# controller_mini.net
KiCad netlist of a schematic drawn in EAGLE
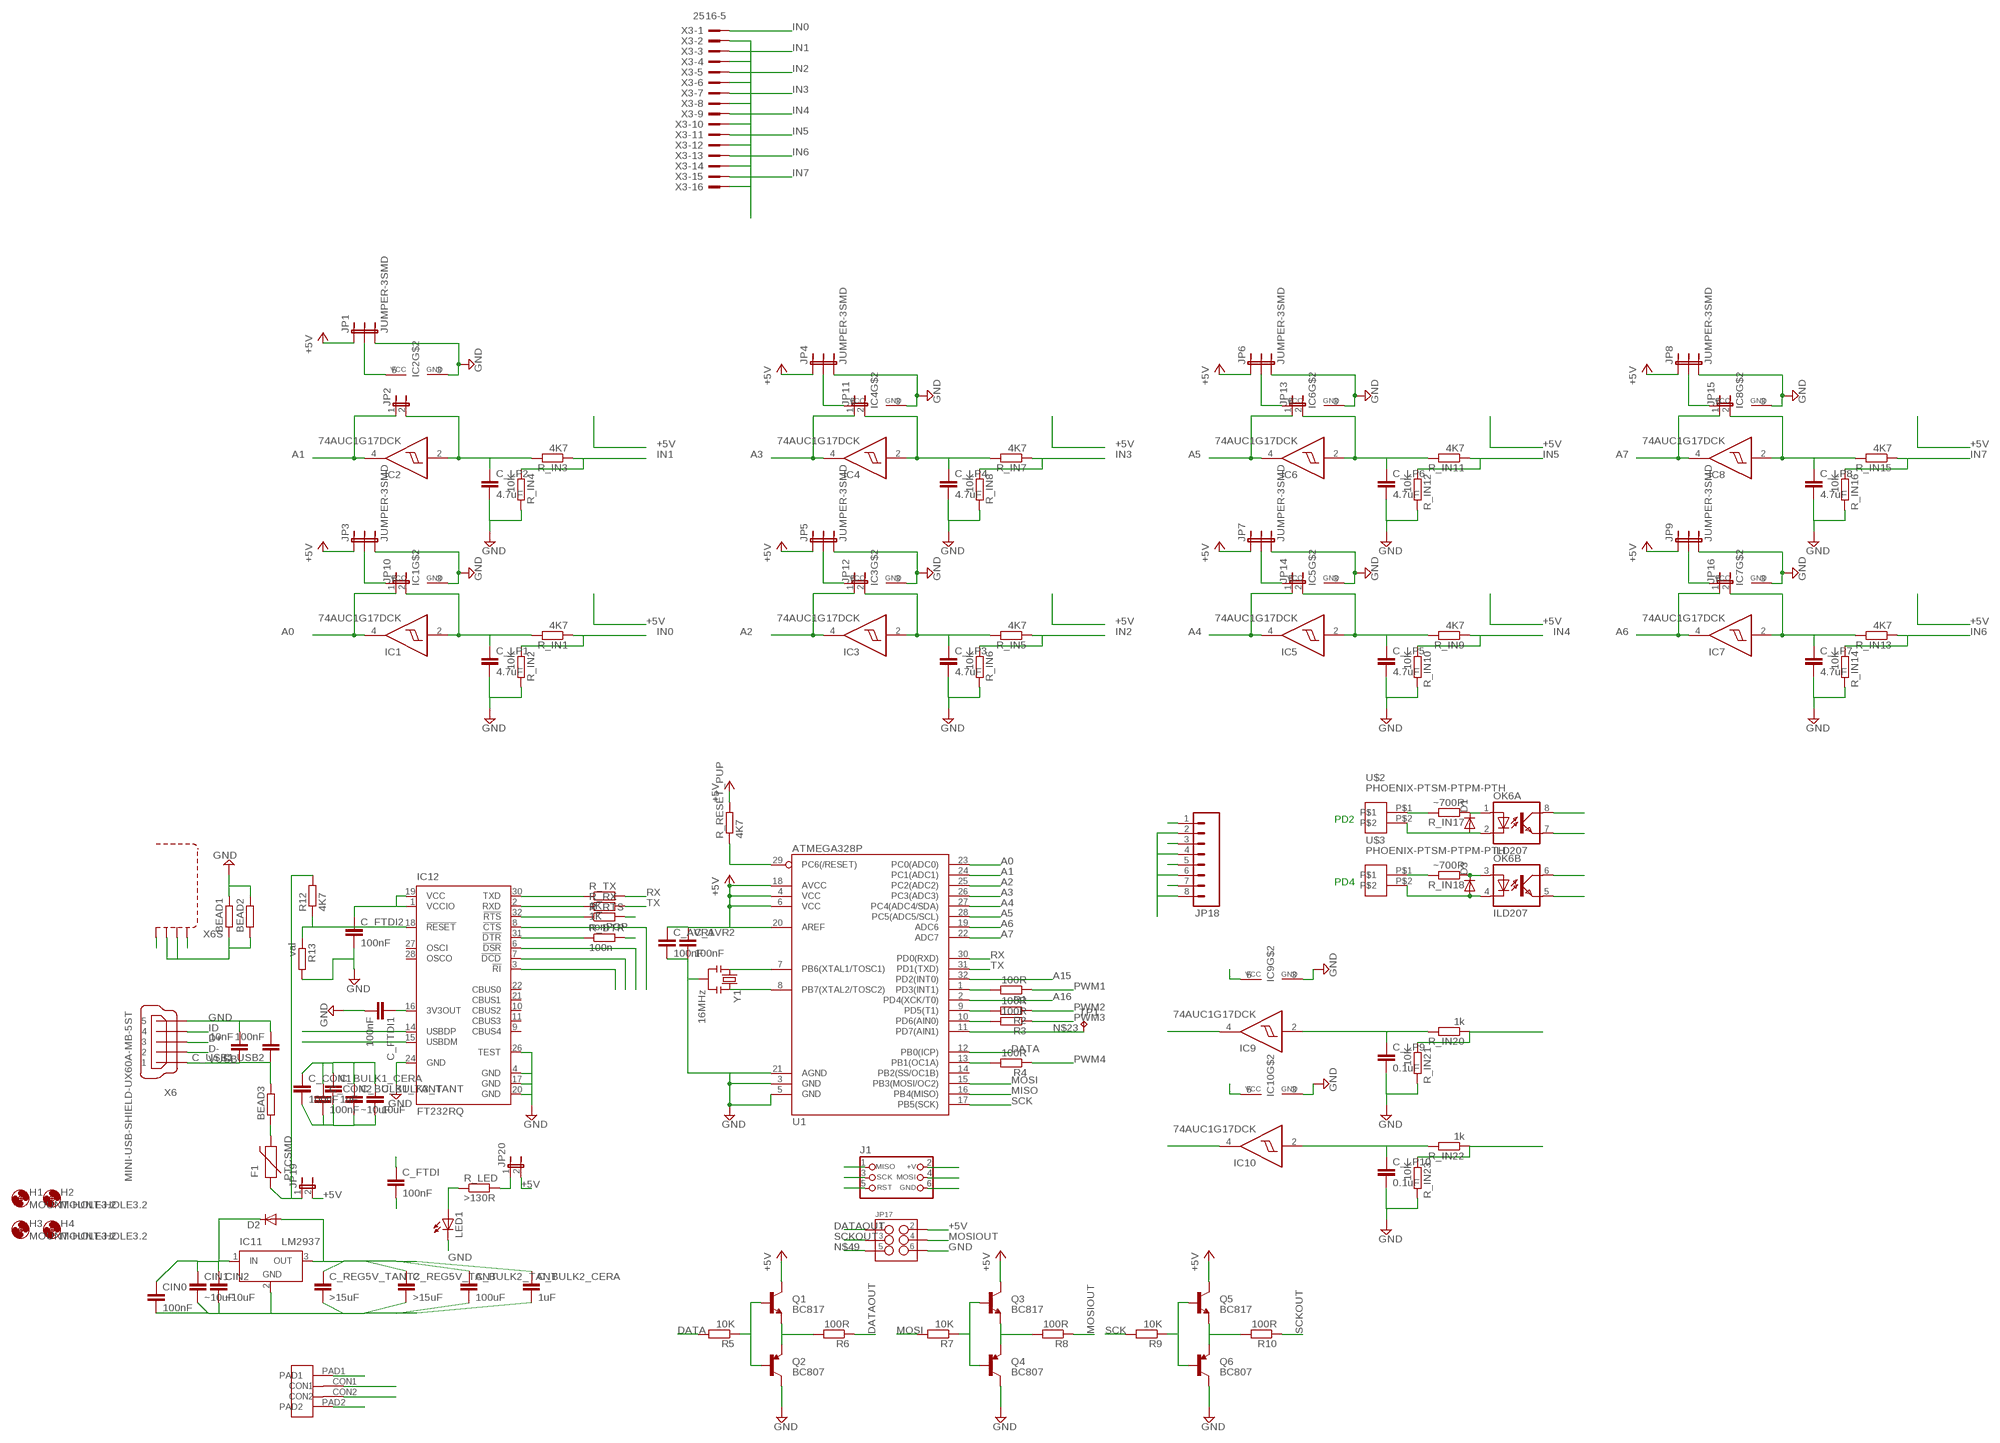
[diagram p0: schematic, sheet 1]

(export (version "E")
  (design (tool "Eeschema 10.0.6"))
  (components
    (comp (ref "BEAD1")
      (value "R-EU_R0805")
      (footprint "eagle-import:R0805")
      (libsource (lib "eagle-import") (part "R-EU_R0805"))
    )
    (comp (ref "BEAD2")
      (value "R-EU_R0805")
      (footprint "eagle-import:R0805")
      (libsource (lib "eagle-import") (part "R-EU_R0805"))
    )
    (comp (ref "BEAD3")
      (value "R-EU_R0805")
      (footprint "eagle-import:R0805")
      (libsource (lib "eagle-import") (part "R-EU_R0805"))
    )
    (comp (ref "CIN0")
      (value "100nF")
      (footprint "eagle-import:C0805")
      (libsource (lib "eagle-import") (part "resistor_C-EUC0805"))
    )
    (comp (ref "CIN1")
      (value "~10uF")
      (footprint "eagle-import:C1210")
      (libsource (lib "eagle-import") (part "resistor_C-EUC1210"))
    )
    (comp (ref "CIN2")
      (value "~10uF")
      (footprint "eagle-import:C1210")
      (libsource (lib "eagle-import") (part "resistor_C-EUC1210"))
    )
    (comp (ref "C_AVR1")
      (value "100nF")
      (footprint "eagle-import:C0805")
      (libsource (lib "eagle-import") (part "resistor_C-EUC0805"))
    )
    (comp (ref "C_AVR2")
      (value "100nF")
      (footprint "eagle-import:C0805")
      (libsource (lib "eagle-import") (part "resistor_C-EUC0805"))
    )
    (comp (ref "C_BULK1_CERA")
      (value "1uF")
      (footprint "eagle-import:C0805K")
      (libsource (lib "eagle-import") (part "resistor_C-EUC0805K"))
    )
    (comp (ref "C_BULK1_TANT")
      (value "~10uF")
      (footprint "eagle-import:C1210")
      (libsource (lib "eagle-import") (part "resistor_C-EUC1210"))
    )
    (comp (ref "C_BULK2_CERA")
      (value "1uF")
      (footprint "eagle-import:C0805K")
      (libsource (lib "eagle-import") (part "resistor_C-EUC0805K"))
    )
    (comp (ref "C_BULK2_TANT")
      (value "100uF")
      (footprint "eagle-import:C1210")
      (libsource (lib "eagle-import") (part "resistor_C-EUC1210"))
    )
    (comp (ref "C_BULK3_TANT")
      (value "10uF")
      (footprint "eagle-import:C1210")
      (libsource (lib "eagle-import") (part "resistor_C-EUC1210"))
    )
    (comp (ref "C_CON1")
      (value "100nF")
      (footprint "eagle-import:C0805")
      (libsource (lib "eagle-import") (part "resistor_C-EUC0805"))
    )
    (comp (ref "C_CON2")
      (value "100nF")
      (footprint "eagle-import:C0805")
      (libsource (lib "eagle-import") (part "resistor_C-EUC0805"))
    )
    (comp (ref "C_FTDI")
      (value "100nF")
      (footprint "eagle-import:C0805")
      (libsource (lib "eagle-import") (part "resistor_C-EUC0805"))
    )
    (comp (ref "C_FTDI1")
      (value "100nF")
      (footprint "eagle-import:C0805")
      (libsource (lib "eagle-import") (part "resistor_C-EUC0805"))
    )
    (comp (ref "C_FTDI2")
      (value "100nF")
      (footprint "eagle-import:C0805")
      (libsource (lib "eagle-import") (part "resistor_C-EUC0805"))
    )
    (comp (ref "C_LP1")
      (value "4.7uF")
      (footprint "eagle-import:C0805")
      (libsource (lib "eagle-import") (part "C-EUC0805"))
    )
    (comp (ref "C_LP2")
      (value "4.7uF")
      (footprint "eagle-import:C0805")
      (libsource (lib "eagle-import") (part "C-EUC0805"))
    )
    (comp (ref "C_LP3")
      (value "4.7uF")
      (footprint "eagle-import:C0805")
      (libsource (lib "eagle-import") (part "C-EUC0805"))
    )
    (comp (ref "C_LP4")
      (value "4.7uF")
      (footprint "eagle-import:C0805")
      (libsource (lib "eagle-import") (part "C-EUC0805"))
    )
    (comp (ref "C_LP5")
      (value "4.7uF")
      (footprint "eagle-import:C0805")
      (libsource (lib "eagle-import") (part "C-EUC0805"))
    )
    (comp (ref "C_LP6")
      (value "4.7uF")
      (footprint "eagle-import:C0805")
      (libsource (lib "eagle-import") (part "C-EUC0805"))
    )
    (comp (ref "C_LP7")
      (value "4.7uF")
      (footprint "eagle-import:C0805")
      (libsource (lib "eagle-import") (part "C-EUC0805"))
    )
    (comp (ref "C_LP8")
      (value "4.7uF")
      (footprint "eagle-import:C0805")
      (libsource (lib "eagle-import") (part "C-EUC0805"))
    )
    (comp (ref "C_LP9")
      (value "0.1uF")
      (footprint "eagle-import:C0805")
      (libsource (lib "eagle-import") (part "C-EUC0805"))
    )
    (comp (ref "C_LP10")
      (value "0.1uF")
      (footprint "eagle-import:C0805")
      (libsource (lib "eagle-import") (part "C-EUC0805"))
    )
    (comp (ref "C_REG5V_TANT")
      (value ">15uF")
      (footprint "eagle-import:C1210")
      (libsource (lib "eagle-import") (part "resistor_C-EUC1210"))
    )
    (comp (ref "C_REG5V_TANT2")
      (value ">15uF")
      (footprint "eagle-import:C1210")
      (libsource (lib "eagle-import") (part "resistor_C-EUC1210"))
    )
    (comp (ref "C_USB1")
      (value "10nF")
      (footprint "eagle-import:C0805")
      (libsource (lib "eagle-import") (part "resistor_C-EUC0805"))
    )
    (comp (ref "C_USB2")
      (value "100nF")
      (footprint "eagle-import:C0805")
      (libsource (lib "eagle-import") (part "resistor_C-EUC0805"))
    )
    (comp (ref "D1")
      (value "DIODE-MICROMELF-W")
      (footprint "eagle-import:MICROMELF-W")
      (libsource (lib "eagle-import") (part "DIODE-MICROMELF-W"))
    )
    (comp (ref "D2")
      (value "DIODESMA")
      (footprint "eagle-import:SMA-DIODE")
      (libsource (lib "eagle-import") (part "DIODESMA"))
    )
    (comp (ref "D3")
      (value "DIODE-MICROMELF-W")
      (footprint "eagle-import:MICROMELF-W")
      (libsource (lib "eagle-import") (part "DIODE-MICROMELF-W"))
    )
    (comp (ref "F1")
      (value "PTCSMD")
      (footprint "eagle-import:PTC-1206")
      (libsource (lib "eagle-import") (part "PTCSMD"))
    )
    (comp (ref "H1")
      (value "MOUNT-HOLE3.2")
      (footprint "eagle-import:3,2")
      (libsource (lib "eagle-import") (part "MOUNT-HOLE3.2"))
    )
    (comp (ref "H2")
      (value "MOUNT-HOLE3.2")
      (footprint "eagle-import:3,2")
      (libsource (lib "eagle-import") (part "MOUNT-HOLE3.2"))
    )
    (comp (ref "H3")
      (value "MOUNT-HOLE3.2")
      (footprint "eagle-import:3,2")
      (libsource (lib "eagle-import") (part "MOUNT-HOLE3.2"))
    )
    (comp (ref "H4")
      (value "MOUNT-HOLE3.2")
      (footprint "eagle-import:3,2")
      (libsource (lib "eagle-import") (part "MOUNT-HOLE3.2"))
    )
    (comp (ref "IC1")
      (value "74AUC1G17DCK")
      (footprint "eagle-import:SC70-5")
      (libsource (lib "eagle-import") (part "741G17DCKAUC"))
    )
    (comp (ref "IC2")
      (value "74AUC1G17DCK")
      (footprint "eagle-import:SC70-5")
      (libsource (lib "eagle-import") (part "741G17DCKAUC"))
    )
    (comp (ref "IC3")
      (value "74AUC1G17DCK")
      (footprint "eagle-import:SC70-5")
      (libsource (lib "eagle-import") (part "741G17DCKAUC"))
    )
    (comp (ref "IC4")
      (value "74AUC1G17DCK")
      (footprint "eagle-import:SC70-5")
      (libsource (lib "eagle-import") (part "741G17DCKAUC"))
    )
    (comp (ref "IC5")
      (value "74AUC1G17DCK")
      (footprint "eagle-import:SC70-5")
      (libsource (lib "eagle-import") (part "741G17DCKAUC"))
    )
    (comp (ref "IC6")
      (value "74AUC1G17DCK")
      (footprint "eagle-import:SC70-5")
      (libsource (lib "eagle-import") (part "741G17DCKAUC"))
    )
    (comp (ref "IC7")
      (value "74AUC1G17DCK")
      (footprint "eagle-import:SC70-5")
      (libsource (lib "eagle-import") (part "741G17DCKAUC"))
    )
    (comp (ref "IC8")
      (value "74AUC1G17DCK")
      (footprint "eagle-import:SC70-5")
      (libsource (lib "eagle-import") (part "741G17DCKAUC"))
    )
    (comp (ref "IC9")
      (value "74AUC1G17DCK")
      (footprint "eagle-import:SC70-5")
      (libsource (lib "eagle-import") (part "741G17DCKAUC"))
    )
    (comp (ref "IC10")
      (value "74AUC1G17DCK")
      (footprint "eagle-import:SC70-5")
      (libsource (lib "eagle-import") (part "741G17DCKAUC"))
    )
    (comp (ref "IC11")
      (value "LM2937")
      (footprint "eagle-import:SOT223")
      (fields (field (name "MPN") "LT1963EST-3.3"))
      (libsource (lib "eagle-import") (part "LT1963EST-3.3"))
    )
    (comp (ref "IC12")
      (value "FT232RQ")
      (footprint "eagle-import:QFN32")
      (libsource (lib "eagle-import") (part "FT232RQ"))
    )
    (comp (ref "J1")
      (value "CON_HEADER_PRG_AVR_ICSP")
      (footprint "eagle-import:HEADER_PRG_2X03")
      (libsource (lib "eagle-import") (part "CON_HEADER_PRG_AVR_ICSP"))
    )
    (comp (ref "JP1")
      (value "JUMPER-3SMD")
      (footprint "eagle-import:SJ_3")
      (libsource (lib "eagle-import") (part "JUMPER-3SMD"))
    )
    (comp (ref "JP2")
      (value "JUMPER-2SMD-NO")
      (footprint "eagle-import:SJ_2S-NO")
      (libsource (lib "eagle-import") (part "JUMPER-2SMD-NO"))
    )
    (comp (ref "JP3")
      (value "JUMPER-3SMD")
      (footprint "eagle-import:SJ_3")
      (libsource (lib "eagle-import") (part "JUMPER-3SMD"))
    )
    (comp (ref "JP4")
      (value "JUMPER-3SMD")
      (footprint "eagle-import:SJ_3")
      (libsource (lib "eagle-import") (part "JUMPER-3SMD"))
    )
    (comp (ref "JP5")
      (value "JUMPER-3SMD")
      (footprint "eagle-import:SJ_3")
      (libsource (lib "eagle-import") (part "JUMPER-3SMD"))
    )
    (comp (ref "JP6")
      (value "JUMPER-3SMD")
      (footprint "eagle-import:SJ_3")
      (libsource (lib "eagle-import") (part "JUMPER-3SMD"))
    )
    (comp (ref "JP7")
      (value "JUMPER-3SMD")
      (footprint "eagle-import:SJ_3")
      (libsource (lib "eagle-import") (part "JUMPER-3SMD"))
    )
    (comp (ref "JP8")
      (value "JUMPER-3SMD")
      (footprint "eagle-import:SJ_3")
      (libsource (lib "eagle-import") (part "JUMPER-3SMD"))
    )
    (comp (ref "JP9")
      (value "JUMPER-3SMD")
      (footprint "eagle-import:SJ_3")
      (libsource (lib "eagle-import") (part "JUMPER-3SMD"))
    )
    (comp (ref "JP10")
      (value "JUMPER-2SMD-NO")
      (footprint "eagle-import:SJ_2S-NO")
      (libsource (lib "eagle-import") (part "JUMPER-2SMD-NO"))
    )
    (comp (ref "JP11")
      (value "JUMPER-2SMD-NO")
      (footprint "eagle-import:SJ_2S-NO")
      (libsource (lib "eagle-import") (part "JUMPER-2SMD-NO"))
    )
    (comp (ref "JP12")
      (value "JUMPER-2SMD-NO")
      (footprint "eagle-import:SJ_2S-NO")
      (libsource (lib "eagle-import") (part "JUMPER-2SMD-NO"))
    )
    (comp (ref "JP13")
      (value "JUMPER-2SMD-NO")
      (footprint "eagle-import:SJ_2S-NO")
      (libsource (lib "eagle-import") (part "JUMPER-2SMD-NO"))
    )
    (comp (ref "JP14")
      (value "JUMPER-2SMD-NO")
      (footprint "eagle-import:SJ_2S-NO")
      (libsource (lib "eagle-import") (part "JUMPER-2SMD-NO"))
    )
    (comp (ref "JP15")
      (value "JUMPER-2SMD-NO")
      (footprint "eagle-import:SJ_2S-NO")
      (libsource (lib "eagle-import") (part "JUMPER-2SMD-NO"))
    )
    (comp (ref "JP16")
      (value "JUMPER-2SMD-NO")
      (footprint "eagle-import:SJ_2S-NO")
      (libsource (lib "eagle-import") (part "JUMPER-2SMD-NO"))
    )
    (comp (ref "JP17")
      (value "M03X2NO_SILK")
      (footprint "eagle-import:2X3-NS")
      (libsource (lib "eagle-import") (part "M03X2NO_SILK"))
    )
    (comp (ref "JP18")
      (value "M08LOCK")
      (footprint "eagle-import:1X08_LOCK")
      (libsource (lib "eagle-import") (part "M08LOCK"))
    )
    (comp (ref "JP19")
      (value "JUMPER-2SMD-NC")
      (footprint "eagle-import:SJ_2S")
      (libsource (lib "eagle-import") (part "JUMPER-2SMD-NC"))
    )
    (comp (ref "JP20")
      (value "JUMPER-2SMD-NC")
      (footprint "eagle-import:SJ_2S")
      (libsource (lib "eagle-import") (part "JUMPER-2SMD-NC"))
    )
    (comp (ref "LED1")
      (value "LEDCHIP-LED0805")
      (footprint "eagle-import:CHIP-LED0805")
      (libsource (lib "eagle-import") (part "LEDCHIP-LED0805"))
    )
    (comp (ref "OK6")
      (value "ILD207")
      (footprint "eagle-import:SOIC08")
      (fields (field (name "MF") "VISHAY/TELEFUNKEN") (field (name "MPN") "ILD207T"))
      (libsource (lib "eagle-import") (part "ILD207"))
    )
    (comp (ref "Q1")
      (value "BC817")
      (footprint "eagle-import:SOT23-3")
      (libsource (lib "eagle-import") (part "TRANSISTOR_NPNSOT23-3"))
    )
    (comp (ref "Q2")
      (value "BC807")
      (footprint "eagle-import:SOT23-3")
      (libsource (lib "eagle-import") (part "TRANSISTOR_PNPSMD"))
    )
    (comp (ref "Q3")
      (value "BC817")
      (footprint "eagle-import:SOT23-3")
      (libsource (lib "eagle-import") (part "TRANSISTOR_NPNSOT23-3"))
    )
    (comp (ref "Q4")
      (value "BC807")
      (footprint "eagle-import:SOT23-3")
      (libsource (lib "eagle-import") (part "TRANSISTOR_PNPSMD"))
    )
    (comp (ref "Q5")
      (value "BC817")
      (footprint "eagle-import:SOT23-3")
      (libsource (lib "eagle-import") (part "TRANSISTOR_NPNSOT23-3"))
    )
    (comp (ref "Q6")
      (value "BC807")
      (footprint "eagle-import:SOT23-3")
      (libsource (lib "eagle-import") (part "TRANSISTOR_PNPSMD"))
    )
    (comp (ref "R1")
      (value "100R")
      (footprint "eagle-import:M0805")
      (libsource (lib "eagle-import") (part "resistor_R-EU_M0805"))
    )
    (comp (ref "R2")
      (value "100R")
      (footprint "eagle-import:M0805")
      (libsource (lib "eagle-import") (part "resistor_R-EU_M0805"))
    )
    (comp (ref "R3")
      (value "100R")
      (footprint "eagle-import:M0805")
      (libsource (lib "eagle-import") (part "resistor_R-EU_M0805"))
    )
    (comp (ref "R4")
      (value "100R")
      (footprint "eagle-import:R0805W")
      (libsource (lib "eagle-import") (part "resistor_R-EU_R0805W"))
    )
    (comp (ref "R5")
      (value "10K")
      (footprint "eagle-import:M0805")
      (libsource (lib "eagle-import") (part "resistor_R-EU_M0805"))
    )
    (comp (ref "R6")
      (value "100R")
      (footprint "eagle-import:M0805")
      (libsource (lib "eagle-import") (part "resistor_R-EU_M0805"))
    )
    (comp (ref "R7")
      (value "10K")
      (footprint "eagle-import:M0805")
      (libsource (lib "eagle-import") (part "resistor_R-EU_M0805"))
    )
    (comp (ref "R8")
      (value "100R")
      (footprint "eagle-import:M0805")
      (libsource (lib "eagle-import") (part "resistor_R-EU_M0805"))
    )
    (comp (ref "R9")
      (value "10K")
      (footprint "eagle-import:M0805")
      (libsource (lib "eagle-import") (part "resistor_R-EU_M0805"))
    )
    (comp (ref "R10")
      (value "100R")
      (footprint "eagle-import:M0805")
      (libsource (lib "eagle-import") (part "resistor_R-EU_M0805"))
    )
    (comp (ref "R12")
      (value "4K7")
      (footprint "eagle-import:R0805")
      (libsource (lib "eagle-import") (part "R-EU_R0805"))
    )
    (comp (ref "R13")
      (value "val")
      (footprint "eagle-import:R0805")
      (libsource (lib "eagle-import") (part "R-EU_R0805"))
    )
    (comp (ref "R_DTR")
      (value "100n")
      (footprint "eagle-import:M0805")
      (libsource (lib "eagle-import") (part "resistor_R-EU_M0805"))
    )
    (comp (ref "R_IN1")
      (value "4K7")
      (footprint "eagle-import:M0805")
      (libsource (lib "eagle-import") (part "R-EU_M0805"))
    )
    (comp (ref "R_IN2")
      (value "10K")
      (footprint "eagle-import:M0805")
      (libsource (lib "eagle-import") (part "R-EU_M0805"))
    )
    (comp (ref "R_IN3")
      (value "4K7")
      (footprint "eagle-import:M0805")
      (libsource (lib "eagle-import") (part "R-EU_M0805"))
    )
    (comp (ref "R_IN4")
      (value "10K")
      (footprint "eagle-import:M0805")
      (libsource (lib "eagle-import") (part "R-EU_M0805"))
    )
    (comp (ref "R_IN5")
      (value "4K7")
      (footprint "eagle-import:M0805")
      (libsource (lib "eagle-import") (part "R-EU_M0805"))
    )
    (comp (ref "R_IN6")
      (value "10K")
      (footprint "eagle-import:M0805")
      (libsource (lib "eagle-import") (part "R-EU_M0805"))
    )
    (comp (ref "R_IN7")
      (value "4K7")
      (footprint "eagle-import:M0805")
      (libsource (lib "eagle-import") (part "R-EU_M0805"))
    )
    (comp (ref "R_IN8")
      (value "10K")
      (footprint "eagle-import:M0805")
      (libsource (lib "eagle-import") (part "R-EU_M0805"))
    )
    (comp (ref "R_IN9")
      (value "4K7")
      (footprint "eagle-import:M0805")
      (libsource (lib "eagle-import") (part "R-EU_M0805"))
    )
    (comp (ref "R_IN10")
      (value "10K")
      (footprint "eagle-import:M0805")
      (libsource (lib "eagle-import") (part "R-EU_M0805"))
    )
    (comp (ref "R_IN11")
      (value "4K7")
      (footprint "eagle-import:M0805")
      (libsource (lib "eagle-import") (part "R-EU_M0805"))
    )
    (comp (ref "R_IN12")
      (value "10K")
      (footprint "eagle-import:M0805")
      (libsource (lib "eagle-import") (part "R-EU_M0805"))
    )
    (comp (ref "R_IN13")
      (value "4K7")
      (footprint "eagle-import:M0805")
      (libsource (lib "eagle-import") (part "R-EU_M0805"))
    )
    (comp (ref "R_IN14")
      (value "10K")
      (footprint "eagle-import:M0805")
      (libsource (lib "eagle-import") (part "R-EU_M0805"))
    )
    (comp (ref "R_IN15")
      (value "4K7")
      (footprint "eagle-import:M0805")
      (libsource (lib "eagle-import") (part "R-EU_M0805"))
    )
    (comp (ref "R_IN16")
      (value "10K")
      (footprint "eagle-import:M0805")
      (libsource (lib "eagle-import") (part "R-EU_M0805"))
    )
    (comp (ref "R_IN17")
      (value "~700R")
      (footprint "eagle-import:M1206")
      (libsource (lib "eagle-import") (part "R-EU_M1206"))
    )
    (comp (ref "R_IN18")
      (value "~700R")
      (footprint "eagle-import:M1206")
      (libsource (lib "eagle-import") (part "R-EU_M1206"))
    )
    (comp (ref "R_IN20")
      (value "1k")
      (footprint "eagle-import:M0805")
      (libsource (lib "eagle-import") (part "R-EU_M0805"))
    )
    (comp (ref "R_IN21")
      (value "10K")
      (footprint "eagle-import:M0805")
      (libsource (lib "eagle-import") (part "R-EU_M0805"))
    )
    (comp (ref "R_IN22")
      (value "1k")
      (footprint "eagle-import:M0805")
      (libsource (lib "eagle-import") (part "R-EU_M0805"))
    )
    (comp (ref "R_IN23")
      (value "10K")
      (footprint "eagle-import:M0805")
      (libsource (lib "eagle-import") (part "R-EU_M0805"))
    )
    (comp (ref "R_LED")
      (value ">130R")
      (footprint "eagle-import:M0805")
      (libsource (lib "eagle-import") (part "resistor_R-EU_M0805"))
    )
    (comp (ref "R_RESET_PUP")
      (value "4K7")
      (footprint "eagle-import:M0805")
      (libsource (lib "eagle-import") (part "resistor_R-EU_M0805"))
    )
    (comp (ref "R_RTS")
      (value "nonPOP")
      (footprint "eagle-import:M0805")
      (libsource (lib "eagle-import") (part "resistor_R-EU_M0805"))
    )
    (comp (ref "R_RX")
      (value "1K")
      (footprint "eagle-import:M0805")
      (libsource (lib "eagle-import") (part "resistor_R-EU_M0805"))
    )
    (comp (ref "R_TX")
      (value "1K")
      (footprint "eagle-import:M0805")
      (libsource (lib "eagle-import") (part "resistor_R-EU_M0805"))
    )
    (comp (ref "TP1")
      (value "TPTP10R")
      (footprint "eagle-import:TP10R")
      (libsource (lib "eagle-import") (part "TPTP10R"))
    )
    (comp (ref "U$1")
      (value "PHOENIX-PTSM-PTPM")
      (footprint "eagle-import:PTSM-SMD-2.5MM-2")
      (libsource (lib "eagle-import") (part "PHOENIX-PTSM-PTPM"))
    )
    (comp (ref "U$2")
      (value "PHOENIX-PTSM-PTPM-PTH")
      (footprint "eagle-import:PTSM-PTH-2.5MM-2")
      (libsource (lib "eagle-import") (part "PHOENIX-PTSM-PTPM-PTH"))
    )
    (comp (ref "U$3")
      (value "PHOENIX-PTSM-PTPM-PTH")
      (footprint "eagle-import:PTSM-PTH-2.5MM-2")
      (libsource (lib "eagle-import") (part "PHOENIX-PTSM-PTPM-PTH"))
    )
    (comp (ref "U1")
      (value "ATMEGA328P")
      (footprint "eagle-import:TQFP32-08")
      (libsource (lib "eagle-import") (part "ATMEGA328_SMT"))
    )
    (comp (ref "X3")
      (value "2516-5")
      (footprint "eagle-import:PAK100_2500-5-16")
      (fields (field (name "MPN") "D2516-5002-AR"))
      (libsource (lib "eagle-import") (part "2516-5"))
    )
    (comp (ref "X6")
      (value "MINI-USB-SHIELD-UX60A-MB-5ST")
      (footprint "eagle-import:UX60A-MB-5ST")
      (libsource (lib "eagle-import") (part "MINI-USB-SHIELD-UX60A-MB-5ST"))
    )
    (comp (ref "Y1")
      (value "16MHz")
      (footprint "eagle-import:RESONATOR-SMD")
      (libsource (lib "eagle-import") (part "RESONATOR16MHZ"))
    )
  )
  (nets
    (net (code "1") (name "+5V") (class "Default")
      (node (ref "C_AVR1") (pin "1") (pinfunction "1_1") (pintype "passive"))
      (node (ref "C_AVR2") (pin "1") (pinfunction "1_1") (pintype "passive"))
      (node (ref "C_BULK1_CERA") (pin "1") (pinfunction "1_1") (pintype "passive"))
      (node (ref "C_BULK1_TANT") (pin "1") (pinfunction "1_1") (pintype "passive"))
      (node (ref "C_BULK2_CERA") (pin "1") (pinfunction "1_1") (pintype "passive"))
      (node (ref "C_BULK2_TANT") (pin "1") (pinfunction "1_1") (pintype "passive"))
      (node (ref "C_BULK3_TANT") (pin "1") (pinfunction "1_1") (pintype "passive"))
      (node (ref "C_CON1") (pin "1") (pinfunction "1_1") (pintype "passive"))
      (node (ref "C_CON2") (pin "1") (pinfunction "1_1") (pintype "passive"))
      (node (ref "C_FTDI") (pin "1") (pinfunction "1_1") (pintype "passive"))
      (node (ref "C_FTDI2") (pin "1") (pinfunction "1_1") (pintype "passive"))
      (node (ref "C_REG5V_TANT") (pin "1") (pinfunction "1_1") (pintype "passive"))
      (node (ref "C_REG5V_TANT2") (pin "1") (pinfunction "1_1") (pintype "passive"))
      (node (ref "D2") (pin "A") (pinfunction "A_A") (pintype "passive"))
      (node (ref "IC10") (pin "5") (pinfunction "VCC_5") (pintype "power_in"))
      (node (ref "IC11") (pin "3") (pinfunction "OUT_3") (pintype "output"))
      (node (ref "IC12") (pin "1") (pinfunction "VCCIO_1") (pintype "power_in"))
      (node (ref "IC12") (pin "19") (pinfunction "VCC_19") (pintype "power_in"))
      (node (ref "IC9") (pin "5") (pinfunction "VCC_5") (pintype "power_in"))
      (node (ref "J1") (pin "2") (pinfunction "+V_2") (pintype "passive"))
      (node (ref "JP1") (pin "1") (pinfunction "1_1") (pintype "passive"))
      (node (ref "JP17") (pin "2") (pinfunction "2_2") (pintype "bidirectional"))
      (node (ref "JP19") (pin "2") (pinfunction "2_2") (pintype "passive"))
      (node (ref "JP20") (pin "2") (pinfunction "2_2") (pintype "passive"))
      (node (ref "JP3") (pin "1") (pinfunction "1_1") (pintype "passive"))
      (node (ref "JP4") (pin "1") (pinfunction "1_1") (pintype "passive"))
      (node (ref "JP5") (pin "1") (pinfunction "1_1") (pintype "passive"))
      (node (ref "JP6") (pin "1") (pinfunction "1_1") (pintype "passive"))
      (node (ref "JP7") (pin "1") (pinfunction "1_1") (pintype "passive"))
      (node (ref "JP8") (pin "1") (pinfunction "1_1") (pintype "passive"))
      (node (ref "JP9") (pin "1") (pinfunction "1_1") (pintype "passive"))
      (node (ref "OK6") (pin "6") (pinfunction "COL_6") (pintype "passive"))
      (node (ref "OK6") (pin "8") (pinfunction "COL_8") (pintype "passive"))
      (node (ref "Q1") (pin "3") (pinfunction "C_3") (pintype "passive"))
      (node (ref "Q3") (pin "3") (pinfunction "C_3") (pintype "passive"))
      (node (ref "Q5") (pin "3") (pinfunction "C_3") (pintype "passive"))
      (node (ref "R_RESET_PUP") (pin "2") (pinfunction "2_2") (pintype "passive"))
      (node (ref "U1") (pin "18") (pinfunction "AVCC_18") (pintype "bidirectional"))
      (node (ref "U1") (pin "20") (pinfunction "AREF_20") (pintype "bidirectional"))
      (node (ref "U1") (pin "4") (pinfunction "VCC_4") (pintype "bidirectional"))
      (node (ref "U1") (pin "6") (pinfunction "VCC_6") (pintype "bidirectional"))
      (node (ref "X3") (pin "10") (pinfunction "KL_10") (pintype "passive"))
      (node (ref "X3") (pin "12") (pinfunction "KL_12") (pintype "passive"))
      (node (ref "X3") (pin "14") (pinfunction "KL_14") (pintype "passive"))
      (node (ref "X3") (pin "16") (pinfunction "KL_16") (pintype "passive"))
      (node (ref "X3") (pin "2") (pinfunction "KL_2") (pintype "passive"))
      (node (ref "X3") (pin "4") (pinfunction "KL_4") (pintype "passive"))
      (node (ref "X3") (pin "6") (pinfunction "KL_6") (pintype "passive"))
      (node (ref "X3") (pin "8") (pinfunction "KL_8") (pintype "passive"))
    )
    (net (code "2") (name "/A0") (class "Default")
      (node (ref "IC1") (pin "4") (pinfunction "O_4") (pintype "output"))
      (node (ref "JP10") (pin "1") (pinfunction "1_1") (pintype "passive"))
      (node (ref "U1") (pin "23") (pinfunction "PC0(ADC0)_23") (pintype "bidirectional"))
    )
    (net (code "3") (name "/A1") (class "Default")
      (node (ref "IC2") (pin "4") (pinfunction "O_4") (pintype "output"))
      (node (ref "JP2") (pin "1") (pinfunction "1_1") (pintype "passive"))
      (node (ref "U1") (pin "24") (pinfunction "PC1(ADC1)_24") (pintype "bidirectional"))
    )
    (net (code "4") (name "/A2") (class "Default")
      (node (ref "IC3") (pin "4") (pinfunction "O_4") (pintype "output"))
      (node (ref "JP12") (pin "1") (pinfunction "1_1") (pintype "passive"))
      (node (ref "U1") (pin "25") (pinfunction "PC2(ADC2)_25") (pintype "bidirectional"))
    )
    (net (code "5") (name "/A3") (class "Default")
      (node (ref "IC4") (pin "4") (pinfunction "O_4") (pintype "output"))
      (node (ref "JP11") (pin "1") (pinfunction "1_1") (pintype "passive"))
      (node (ref "U1") (pin "26") (pinfunction "PC3(ADC3)_26") (pintype "bidirectional"))
    )
    (net (code "6") (name "/A4") (class "Default")
      (node (ref "IC5") (pin "4") (pinfunction "O_4") (pintype "output"))
      (node (ref "JP14") (pin "1") (pinfunction "1_1") (pintype "passive"))
      (node (ref "U1") (pin "27") (pinfunction "PC4(ADC4/SDA)_27") (pintype "bidirectional"))
    )
    (net (code "7") (name "/A5") (class "Default")
      (node (ref "IC6") (pin "4") (pinfunction "O_4") (pintype "output"))
      (node (ref "JP13") (pin "1") (pinfunction "1_1") (pintype "passive"))
      (node (ref "U1") (pin "28") (pinfunction "PC5(ADC5/SCL)_28") (pintype "bidirectional"))
    )
    (net (code "8") (name "/A6") (class "Default")
      (node (ref "IC7") (pin "4") (pinfunction "O_4") (pintype "output"))
      (node (ref "JP16") (pin "1") (pinfunction "1_1") (pintype "passive"))
      (node (ref "U1") (pin "19") (pinfunction "ADC6_19") (pintype "bidirectional"))
    )
    (net (code "9") (name "/A7") (class "Default")
      (node (ref "IC8") (pin "4") (pinfunction "O_4") (pintype "output"))
      (node (ref "JP15") (pin "1") (pinfunction "1_1") (pintype "passive"))
      (node (ref "U1") (pin "22") (pinfunction "ADC7_22") (pintype "bidirectional"))
    )
    (net (code "10") (name "/A15") (class "Default")
      (node (ref "IC9") (pin "4") (pinfunction "O_4") (pintype "output"))
      (node (ref "U1") (pin "32") (pinfunction "PD2(INT0)_32") (pintype "bidirectional"))
    )
    (net (code "11") (name "/A16") (class "Default")
      (node (ref "IC10") (pin "4") (pinfunction "O_4") (pintype "output"))
      (node (ref "U1") (pin "2") (pinfunction "PD4(XCK/T0)_2") (pintype "bidirectional"))
    )
    (net (code "12") (name "/D+") (class "Default")
      (node (ref "IC12") (pin "14") (pinfunction "USBDP_14") (pintype "bidirectional"))
      (node (ref "X6") (pin "3") (pinfunction "3_3") (pintype "input"))
    )
    (net (code "13") (name "/D-") (class "Default")
      (node (ref "IC12") (pin "15") (pinfunction "USBDM_15") (pintype "bidirectional"))
      (node (ref "X6") (pin "2") (pinfunction "2_2") (pintype "input"))
    )
    (net (code "14") (name "/DATA") (class "Default")
      (node (ref "R5") (pin "2") (pinfunction "2_2") (pintype "passive"))
      (node (ref "U1") (pin "12") (pinfunction "PB0(ICP)_12") (pintype "bidirectional"))
    )
    (net (code "15") (name "/DATAOUT") (class "Default")
      (node (ref "JP17") (pin "1") (pinfunction "1_1") (pintype "bidirectional"))
      (node (ref "R6") (pin "1") (pinfunction "1_1") (pintype "passive"))
    )
    (net (code "16") (name "/ID") (class "Default")
      (node (ref "X6") (pin "4") (pinfunction "4_4") (pintype "input"))
    )
    (net (code "17") (name "/IN0") (class "Default")
      (node (ref "R_IN1") (pin "1") (pinfunction "1_1") (pintype "passive"))
      (node (ref "R_IN2") (pin "1") (pinfunction "1_1") (pintype "passive"))
      (node (ref "X3") (pin "1") (pinfunction "KL_1") (pintype "passive"))
    )
    (net (code "18") (name "/IN1") (class "Default")
      (node (ref "R_IN3") (pin "1") (pinfunction "1_1") (pintype "passive"))
      (node (ref "R_IN4") (pin "1") (pinfunction "1_1") (pintype "passive"))
      (node (ref "X3") (pin "3") (pinfunction "KL_3") (pintype "passive"))
    )
    (net (code "19") (name "/IN2") (class "Default")
      (node (ref "R_IN5") (pin "1") (pinfunction "1_1") (pintype "passive"))
      (node (ref "R_IN6") (pin "1") (pinfunction "1_1") (pintype "passive"))
      (node (ref "X3") (pin "5") (pinfunction "KL_5") (pintype "passive"))
    )
    (net (code "20") (name "/IN3") (class "Default")
      (node (ref "R_IN7") (pin "1") (pinfunction "1_1") (pintype "passive"))
      (node (ref "R_IN8") (pin "1") (pinfunction "1_1") (pintype "passive"))
      (node (ref "X3") (pin "7") (pinfunction "KL_7") (pintype "passive"))
    )
    (net (code "21") (name "/IN4") (class "Default")
      (node (ref "R_IN10") (pin "1") (pinfunction "1_1") (pintype "passive"))
      (node (ref "R_IN9") (pin "1") (pinfunction "1_1") (pintype "passive"))
      (node (ref "X3") (pin "9") (pinfunction "KL_9") (pintype "passive"))
    )
    (net (code "22") (name "/IN5") (class "Default")
      (node (ref "R_IN11") (pin "1") (pinfunction "1_1") (pintype "passive"))
      (node (ref "R_IN12") (pin "1") (pinfunction "1_1") (pintype "passive"))
      (node (ref "X3") (pin "11") (pinfunction "KL_11") (pintype "passive"))
    )
    (net (code "23") (name "/IN6") (class "Default")
      (node (ref "R_IN13") (pin "1") (pinfunction "1_1") (pintype "passive"))
      (node (ref "R_IN14") (pin "1") (pinfunction "1_1") (pintype "passive"))
      (node (ref "X3") (pin "13") (pinfunction "KL_13") (pintype "passive"))
    )
    (net (code "24") (name "/IN7") (class "Default")
      (node (ref "R_IN15") (pin "1") (pinfunction "1_1") (pintype "passive"))
      (node (ref "R_IN16") (pin "1") (pinfunction "1_1") (pintype "passive"))
      (node (ref "X3") (pin "15") (pinfunction "KL_15") (pintype "passive"))
    )
    (net (code "25") (name "/MISO") (class "Default")
      (node (ref "J1") (pin "1") (pinfunction "MISO_1") (pintype "passive"))
      (node (ref "U1") (pin "16") (pinfunction "PB4(MISO)_16") (pintype "bidirectional"))
    )
    (net (code "26") (name "/MOSI") (class "Default")
      (node (ref "J1") (pin "4") (pinfunction "MOSI_4") (pintype "passive"))
      (node (ref "R7") (pin "2") (pinfunction "2_2") (pintype "passive"))
      (node (ref "U1") (pin "15") (pinfunction "PB3(MOSI/OC2)_15") (pintype "bidirectional"))
    )
    (net (code "27") (name "/MOSIOUT") (class "Default")
      (node (ref "JP17") (pin "4") (pinfunction "4_4") (pintype "bidirectional"))
      (node (ref "R8") (pin "1") (pinfunction "1_1") (pintype "passive"))
    )
    (net (code "28") (name "/N$21") (class "Default")
      (node (ref "OK6") (pin "7") (pinfunction "EMIT_7") (pintype "passive"))
      (node (ref "R_IN20") (pin "1") (pinfunction "1_1") (pintype "passive"))
      (node (ref "R_IN21") (pin "1") (pinfunction "1_1") (pintype "passive"))
    )
    (net (code "29") (name "/N$22") (class "Default")
      (node (ref "OK6") (pin "5") (pinfunction "EMIT_5") (pintype "passive"))
      (node (ref "R_IN22") (pin "1") (pinfunction "1_1") (pintype "passive"))
      (node (ref "R_IN23") (pin "1") (pinfunction "1_1") (pintype "passive"))
    )
    (net (code "30") (name "/N$23") (class "Default")
      (node (ref "TP1") (pin "TP") (pinfunction "TP_TP") (pintype "input"))
      (node (ref "U1") (pin "11") (pinfunction "PD7(AIN1)_11") (pintype "bidirectional"))
    )
    (net (code "31") (name "/N$49") (class "Default")
      (node (ref "JP17") (pin "5") (pinfunction "5_5") (pintype "bidirectional"))
    )
    (net (code "32") (name "/PWM1") (class "Default")
      (node (ref "JP18") (pin "1") (pinfunction "1_1") (pintype "passive"))
      (node (ref "R1") (pin "1") (pinfunction "1_1") (pintype "passive"))
    )
    (net (code "33") (name "/PWM2") (class "Default")
      (node (ref "JP18") (pin "3") (pinfunction "3_3") (pintype "passive"))
      (node (ref "R2") (pin "1") (pinfunction "1_1") (pintype "passive"))
    )
    (net (code "34") (name "/PWM3") (class "Default")
      (node (ref "JP18") (pin "5") (pinfunction "5_5") (pintype "passive"))
      (node (ref "R3") (pin "1") (pinfunction "1_1") (pintype "passive"))
    )
    (net (code "35") (name "/PWM4") (class "Default")
      (node (ref "JP18") (pin "7") (pinfunction "7_7") (pintype "passive"))
      (node (ref "R4") (pin "1") (pinfunction "1_1") (pintype "passive"))
    )
    (net (code "36") (name "/RESET") (class "Default")
      (node (ref "J1") (pin "5") (pinfunction "RST_5") (pintype "passive"))
      (node (ref "R_DTR") (pin "2") (pinfunction "2_2") (pintype "passive"))
      (node (ref "R_RESET_PUP") (pin "1") (pinfunction "1_1") (pintype "passive"))
      (node (ref "R_RTS") (pin "2") (pinfunction "2_2") (pintype "passive"))
      (node (ref "U1") (pin "29") (pinfunction "PC6(/RESET)_29") (pintype "bidirectional"))
    )
    (net (code "37") (name "/RX") (class "Default")
      (node (ref "R_TX") (pin "2") (pinfunction "2_2") (pintype "passive"))
      (node (ref "U1") (pin "30") (pinfunction "PD0(RXD)_30") (pintype "bidirectional"))
    )
    (net (code "38") (name "/SCK") (class "Default")
      (node (ref "J1") (pin "3") (pinfunction "SCK_3") (pintype "passive"))
      (node (ref "R9") (pin "2") (pinfunction "2_2") (pintype "passive"))
      (node (ref "U1") (pin "17") (pinfunction "PB5(SCK)_17") (pintype "bidirectional"))
    )
    (net (code "39") (name "/SCKOUT") (class "Default")
      (node (ref "JP17") (pin "3") (pinfunction "3_3") (pintype "bidirectional"))
      (node (ref "R10") (pin "1") (pinfunction "1_1") (pintype "passive"))
    )
    (net (code "40") (name "/TX") (class "Default")
      (node (ref "R_RX") (pin "2") (pinfunction "2_2") (pintype "passive"))
      (node (ref "U1") (pin "31") (pinfunction "PD1(TXD)_31") (pintype "bidirectional"))
    )
    (net (code "41") (name "/VIN") (class "Default")
      (node (ref "CIN0") (pin "1") (pinfunction "1_1") (pintype "passive"))
      (node (ref "CIN1") (pin "1") (pinfunction "1_1") (pintype "passive"))
      (node (ref "CIN2") (pin "1") (pinfunction "1_1") (pintype "passive"))
      (node (ref "D2") (pin "C") (pinfunction "C_C") (pintype "passive"))
      (node (ref "IC11") (pin "1") (pinfunction "IN_1") (pintype "input"))
      (node (ref "U$1") (pin "CON1") (pinfunction "CON1_CON1") (pintype "bidirectional"))
    )
    (net (code "42") (name "/VUSB") (class "Default")
      (node (ref "BEAD3") (pin "2") (pinfunction "2_2") (pintype "passive"))
      (node (ref "C_USB1") (pin "1") (pinfunction "1_1") (pintype "passive"))
      (node (ref "C_USB2") (pin "1") (pinfunction "1_1") (pintype "passive"))
      (node (ref "X6") (pin "1") (pinfunction "1_1") (pintype "input"))
    )
    (net (code "43") (name "GND") (class "Default")
      (node (ref "BEAD1") (pin "2") (pinfunction "2_2") (pintype "passive"))
      (node (ref "BEAD2") (pin "2") (pinfunction "2_2") (pintype "passive"))
      (node (ref "CIN0") (pin "2") (pinfunction "2_2") (pintype "passive"))
      (node (ref "CIN1") (pin "2") (pinfunction "2_2") (pintype "passive"))
      (node (ref "CIN2") (pin "2") (pinfunction "2_2") (pintype "passive"))
      (node (ref "C_AVR1") (pin "2") (pinfunction "2_2") (pintype "passive"))
      (node (ref "C_AVR2") (pin "2") (pinfunction "2_2") (pintype "passive"))
      (node (ref "C_BULK1_CERA") (pin "2") (pinfunction "2_2") (pintype "passive"))
      (node (ref "C_BULK1_TANT") (pin "2") (pinfunction "2_2") (pintype "passive"))
      (node (ref "C_BULK2_CERA") (pin "2") (pinfunction "2_2") (pintype "passive"))
      (node (ref "C_BULK2_TANT") (pin "2") (pinfunction "2_2") (pintype "passive"))
      (node (ref "C_BULK3_TANT") (pin "2") (pinfunction "2_2") (pintype "passive"))
      (node (ref "C_CON1") (pin "2") (pinfunction "2_2") (pintype "passive"))
      (node (ref "C_CON2") (pin "2") (pinfunction "2_2") (pintype "passive"))
      (node (ref "C_FTDI") (pin "2") (pinfunction "2_2") (pintype "passive"))
      (node (ref "C_FTDI1") (pin "2") (pinfunction "2_2") (pintype "passive"))
      (node (ref "C_FTDI2") (pin "2") (pinfunction "2_2") (pintype "passive"))
      (node (ref "C_LP1") (pin "2") (pinfunction "2_2") (pintype "passive"))
      (node (ref "C_LP10") (pin "2") (pinfunction "2_2") (pintype "passive"))
      (node (ref "C_LP2") (pin "2") (pinfunction "2_2") (pintype "passive"))
      (node (ref "C_LP3") (pin "2") (pinfunction "2_2") (pintype "passive"))
      (node (ref "C_LP4") (pin "2") (pinfunction "2_2") (pintype "passive"))
      (node (ref "C_LP5") (pin "2") (pinfunction "2_2") (pintype "passive"))
      (node (ref "C_LP6") (pin "2") (pinfunction "2_2") (pintype "passive"))
      (node (ref "C_LP7") (pin "2") (pinfunction "2_2") (pintype "passive"))
      (node (ref "C_LP8") (pin "2") (pinfunction "2_2") (pintype "passive"))
      (node (ref "C_LP9") (pin "2") (pinfunction "2_2") (pintype "passive"))
      (node (ref "C_REG5V_TANT") (pin "2") (pinfunction "2_2") (pintype "passive"))
      (node (ref "C_REG5V_TANT2") (pin "2") (pinfunction "2_2") (pintype "passive"))
      (node (ref "C_USB1") (pin "2") (pinfunction "2_2") (pintype "passive"))
      (node (ref "C_USB2") (pin "2") (pinfunction "2_2") (pintype "passive"))
      (node (ref "IC1") (pin "3") (pinfunction "GND_3") (pintype "power_in"))
      (node (ref "IC10") (pin "3") (pinfunction "GND_3") (pintype "power_in"))
      (node (ref "IC11") (pin "2") (pinfunction "GND_2") (pintype "power_in"))
      (node (ref "IC12") (pin "17") (pinfunction "GND_17") (pintype "power_in"))
      (node (ref "IC12") (pin "20") (pinfunction "GND_20") (pintype "power_in"))
      (node (ref "IC12") (pin "24") (pinfunction "GND_24") (pintype "power_in"))
      (node (ref "IC12") (pin "26") (pinfunction "TEST_26") (pintype "input"))
      (node (ref "IC12") (pin "4") (pinfunction "GND_4") (pintype "power_in"))
      (node (ref "IC2") (pin "3") (pinfunction "GND_3") (pintype "power_in"))
      (node (ref "IC3") (pin "3") (pinfunction "GND_3") (pintype "power_in"))
      (node (ref "IC4") (pin "3") (pinfunction "GND_3") (pintype "power_in"))
      (node (ref "IC5") (pin "3") (pinfunction "GND_3") (pintype "power_in"))
      (node (ref "IC6") (pin "3") (pinfunction "GND_3") (pintype "power_in"))
      (node (ref "IC7") (pin "3") (pinfunction "GND_3") (pintype "power_in"))
      (node (ref "IC8") (pin "3") (pinfunction "GND_3") (pintype "power_in"))
      (node (ref "IC9") (pin "3") (pinfunction "GND_3") (pintype "power_in"))
      (node (ref "J1") (pin "6") (pinfunction "GND_6") (pintype "passive"))
      (node (ref "JP1") (pin "3") (pinfunction "3_3") (pintype "passive"))
      (node (ref "JP17") (pin "6") (pinfunction "6_6") (pintype "bidirectional"))
      (node (ref "JP18") (pin "2") (pinfunction "2_2") (pintype "passive"))
      (node (ref "JP18") (pin "4") (pinfunction "4_4") (pintype "passive"))
      (node (ref "JP18") (pin "6") (pinfunction "6_6") (pintype "passive"))
      (node (ref "JP18") (pin "8") (pinfunction "8_8") (pintype "passive"))
      (node (ref "JP3") (pin "3") (pinfunction "3_3") (pintype "passive"))
      (node (ref "JP4") (pin "3") (pinfunction "3_3") (pintype "passive"))
      (node (ref "JP5") (pin "3") (pinfunction "3_3") (pintype "passive"))
      (node (ref "JP6") (pin "3") (pinfunction "3_3") (pintype "passive"))
      (node (ref "JP7") (pin "3") (pinfunction "3_3") (pintype "passive"))
      (node (ref "JP8") (pin "3") (pinfunction "3_3") (pintype "passive"))
      (node (ref "JP9") (pin "3") (pinfunction "3_3") (pintype "passive"))
      (node (ref "LED1") (pin "C") (pinfunction "C_C") (pintype "passive"))
      (node (ref "Q2") (pin "3") (pinfunction "C_3") (pintype "passive"))
      (node (ref "Q4") (pin "3") (pinfunction "C_3") (pintype "passive"))
      (node (ref "Q6") (pin "3") (pinfunction "C_3") (pintype "passive"))
      (node (ref "R13") (pin "2") (pinfunction "2_2") (pintype "passive"))
      (node (ref "R_IN10") (pin "2") (pinfunction "2_2") (pintype "passive"))
      (node (ref "R_IN12") (pin "2") (pinfunction "2_2") (pintype "passive"))
      (node (ref "R_IN14") (pin "2") (pinfunction "2_2") (pintype "passive"))
      (node (ref "R_IN16") (pin "2") (pinfunction "2_2") (pintype "passive"))
      (node (ref "R_IN2") (pin "2") (pinfunction "2_2") (pintype "passive"))
      (node (ref "R_IN21") (pin "2") (pinfunction "2_2") (pintype "passive"))
      (node (ref "R_IN23") (pin "2") (pinfunction "2_2") (pintype "passive"))
      (node (ref "R_IN4") (pin "2") (pinfunction "2_2") (pintype "passive"))
      (node (ref "R_IN6") (pin "2") (pinfunction "2_2") (pintype "passive"))
      (node (ref "R_IN8") (pin "2") (pinfunction "2_2") (pintype "passive"))
      (node (ref "U$1") (pin "CON2") (pinfunction "CON2_CON2") (pintype "bidirectional"))
      (node (ref "U$1") (pin "PAD1") (pinfunction "PAD1_PAD1") (pintype "bidirectional"))
      (node (ref "U$1") (pin "PAD2") (pinfunction "PAD2_PAD2") (pintype "bidirectional"))
      (node (ref "U1") (pin "21") (pinfunction "AGND_21") (pintype "bidirectional"))
      (node (ref "U1") (pin "3") (pinfunction "GND_3") (pintype "bidirectional"))
      (node (ref "U1") (pin "5") (pinfunction "GND_5") (pintype "bidirectional"))
      (node (ref "X6") (pin "5") (pinfunction "5_5") (pintype "input"))
      (node (ref "Y1") (pin "2") (pinfunction "2_2") (pintype "passive"))
    )
    (net (code "44") (name "Net-(BEAD3-Pad1)") (class "Default")
      (node (ref "BEAD3") (pin "1") (pinfunction "1_1") (pintype "passive"))
      (node (ref "F1") (pin "2") (pinfunction "2_2") (pintype "bidirectional"))
    )
    (net (code "45") (name "Net-(F1-Pad1)") (class "Default")
      (node (ref "F1") (pin "1") (pinfunction "1_1") (pintype "bidirectional"))
      (node (ref "JP19") (pin "1") (pinfunction "1_1") (pintype "passive"))
      (node (ref "R12") (pin "2") (pinfunction "2_2") (pintype "passive"))
    )
    (net (code "46") (name "Net-(IC1A-I)") (class "Default")
      (node (ref "C_LP1") (pin "1") (pinfunction "1_1") (pintype "passive"))
      (node (ref "IC1") (pin "2") (pinfunction "I_2") (pintype "input"))
      (node (ref "JP10") (pin "2") (pinfunction "2_2") (pintype "passive"))
      (node (ref "R_IN1") (pin "2") (pinfunction "2_2") (pintype "passive"))
    )
    (net (code "47") (name "Net-(IC1B-VCC)") (class "Default")
      (node (ref "IC1") (pin "5") (pinfunction "VCC_5") (pintype "power_in"))
      (node (ref "JP3") (pin "2") (pinfunction "2_2") (pintype "passive"))
    )
    (net (code "48") (name "Net-(IC2A-I)") (class "Default")
      (node (ref "C_LP2") (pin "1") (pinfunction "1_1") (pintype "passive"))
      (node (ref "IC2") (pin "2") (pinfunction "I_2") (pintype "input"))
      (node (ref "JP2") (pin "2") (pinfunction "2_2") (pintype "passive"))
      (node (ref "R_IN3") (pin "2") (pinfunction "2_2") (pintype "passive"))
    )
    (net (code "49") (name "Net-(IC2B-VCC)") (class "Default")
      (node (ref "IC2") (pin "5") (pinfunction "VCC_5") (pintype "power_in"))
      (node (ref "JP1") (pin "2") (pinfunction "2_2") (pintype "passive"))
    )
    (net (code "50") (name "Net-(IC3A-I)") (class "Default")
      (node (ref "C_LP3") (pin "1") (pinfunction "1_1") (pintype "passive"))
      (node (ref "IC3") (pin "2") (pinfunction "I_2") (pintype "input"))
      (node (ref "JP12") (pin "2") (pinfunction "2_2") (pintype "passive"))
      (node (ref "R_IN5") (pin "2") (pinfunction "2_2") (pintype "passive"))
    )
    (net (code "51") (name "Net-(IC3B-VCC)") (class "Default")
      (node (ref "IC3") (pin "5") (pinfunction "VCC_5") (pintype "power_in"))
      (node (ref "JP5") (pin "2") (pinfunction "2_2") (pintype "passive"))
    )
    (net (code "52") (name "Net-(IC4A-I)") (class "Default")
      (node (ref "C_LP4") (pin "1") (pinfunction "1_1") (pintype "passive"))
      (node (ref "IC4") (pin "2") (pinfunction "I_2") (pintype "input"))
      (node (ref "JP11") (pin "2") (pinfunction "2_2") (pintype "passive"))
      (node (ref "R_IN7") (pin "2") (pinfunction "2_2") (pintype "passive"))
    )
    (net (code "53") (name "Net-(IC4B-VCC)") (class "Default")
      (node (ref "IC4") (pin "5") (pinfunction "VCC_5") (pintype "power_in"))
      (node (ref "JP4") (pin "2") (pinfunction "2_2") (pintype "passive"))
    )
    (net (code "54") (name "Net-(IC5A-I)") (class "Default")
      (node (ref "C_LP5") (pin "1") (pinfunction "1_1") (pintype "passive"))
      (node (ref "IC5") (pin "2") (pinfunction "I_2") (pintype "input"))
      (node (ref "JP14") (pin "2") (pinfunction "2_2") (pintype "passive"))
      (node (ref "R_IN9") (pin "2") (pinfunction "2_2") (pintype "passive"))
    )
    (net (code "55") (name "Net-(IC5B-VCC)") (class "Default")
      (node (ref "IC5") (pin "5") (pinfunction "VCC_5") (pintype "power_in"))
      (node (ref "JP7") (pin "2") (pinfunction "2_2") (pintype "passive"))
    )
    (net (code "56") (name "Net-(IC6A-I)") (class "Default")
      (node (ref "C_LP6") (pin "1") (pinfunction "1_1") (pintype "passive"))
      (node (ref "IC6") (pin "2") (pinfunction "I_2") (pintype "input"))
      (node (ref "JP13") (pin "2") (pinfunction "2_2") (pintype "passive"))
      (node (ref "R_IN11") (pin "2") (pinfunction "2_2") (pintype "passive"))
    )
    (net (code "57") (name "Net-(IC6B-VCC)") (class "Default")
      (node (ref "IC6") (pin "5") (pinfunction "VCC_5") (pintype "power_in"))
      (node (ref "JP6") (pin "2") (pinfunction "2_2") (pintype "passive"))
    )
    (net (code "58") (name "Net-(IC7A-I)") (class "Default")
      (node (ref "C_LP7") (pin "1") (pinfunction "1_1") (pintype "passive"))
      (node (ref "IC7") (pin "2") (pinfunction "I_2") (pintype "input"))
      (node (ref "JP16") (pin "2") (pinfunction "2_2") (pintype "passive"))
      (node (ref "R_IN13") (pin "2") (pinfunction "2_2") (pintype "passive"))
    )
    (net (code "59") (name "Net-(IC7B-VCC)") (class "Default")
      (node (ref "IC7") (pin "5") (pinfunction "VCC_5") (pintype "power_in"))
      (node (ref "JP9") (pin "2") (pinfunction "2_2") (pintype "passive"))
    )
    (net (code "60") (name "Net-(IC8A-I)") (class "Default")
      (node (ref "C_LP8") (pin "1") (pinfunction "1_1") (pintype "passive"))
      (node (ref "IC8") (pin "2") (pinfunction "I_2") (pintype "input"))
      (node (ref "JP15") (pin "2") (pinfunction "2_2") (pintype "passive"))
      (node (ref "R_IN15") (pin "2") (pinfunction "2_2") (pintype "passive"))
    )
    (net (code "61") (name "Net-(IC8B-VCC)") (class "Default")
      (node (ref "IC8") (pin "5") (pinfunction "VCC_5") (pintype "power_in"))
      (node (ref "JP8") (pin "2") (pinfunction "2_2") (pintype "passive"))
    )
    (net (code "62") (name "Net-(IC9A-I)") (class "Default")
      (node (ref "C_LP9") (pin "1") (pinfunction "1_1") (pintype "passive"))
      (node (ref "IC9") (pin "2") (pinfunction "I_2") (pintype "input"))
      (node (ref "R_IN20") (pin "2") (pinfunction "2_2") (pintype "passive"))
    )
    (net (code "63") (name "Net-(IC10A-I)") (class "Default")
      (node (ref "C_LP10") (pin "1") (pinfunction "1_1") (pintype "passive"))
      (node (ref "IC10") (pin "2") (pinfunction "I_2") (pintype "input"))
      (node (ref "R_IN22") (pin "2") (pinfunction "2_2") (pintype "passive"))
    )
    (net (code "64") (name "Net-(IC12-3V3OUT)") (class "Default")
      (node (ref "C_FTDI1") (pin "1") (pinfunction "1_1") (pintype "passive"))
      (node (ref "IC12") (pin "16") (pinfunction "3V3OUT_16") (pintype "output"))
    )
    (net (code "65") (name "Net-(IC12-RXD)") (class "Default")
      (node (ref "IC12") (pin "2") (pinfunction "RXD_2") (pintype "input"))
      (node (ref "R_RX") (pin "1") (pinfunction "1_1") (pintype "passive"))
    )
    (net (code "66") (name "Net-(IC12-TXD)") (class "Default")
      (node (ref "IC12") (pin "30") (pinfunction "TXD_30") (pintype "output"))
      (node (ref "R_TX") (pin "1") (pinfunction "1_1") (pintype "passive"))
    )
    (net (code "67") (name "Net-(IC12-~{DTR})") (class "Default")
      (node (ref "IC12") (pin "31") (pinfunction "~{DTR}_31") (pintype "output"))
      (node (ref "R_DTR") (pin "1") (pinfunction "1_1") (pintype "passive"))
    )
    (net (code "68") (name "Net-(IC12-~{RESET})") (class "Default")
      (node (ref "IC12") (pin "18") (pinfunction "~{RESET}_18") (pintype "input"))
      (node (ref "R12") (pin "1") (pinfunction "1_1") (pintype "passive"))
      (node (ref "R13") (pin "1") (pinfunction "1_1") (pintype "passive"))
    )
    (net (code "69") (name "Net-(IC12-~{RTS})") (class "Default")
      (node (ref "IC12") (pin "32") (pinfunction "~{RTS}_32") (pintype "output"))
      (node (ref "R_RTS") (pin "1") (pinfunction "1_1") (pintype "passive"))
    )
    (net (code "70") (name "Net-(JP20-Pad1)") (class "Default")
      (node (ref "JP20") (pin "1") (pinfunction "1_1") (pintype "passive"))
      (node (ref "R_LED") (pin "2") (pinfunction "2_2") (pintype "passive"))
    )
    (net (code "71") (name "Net-(LED1-PadA)") (class "Default")
      (node (ref "LED1") (pin "A") (pinfunction "A_A") (pintype "passive"))
      (node (ref "R_LED") (pin "1") (pinfunction "1_1") (pintype "passive"))
    )
    (net (code "72") (name "Net-(OK6A-A)") (class "Default")
      (node (ref "D1") (pin "C") (pinfunction "C_C") (pintype "passive"))
      (node (ref "OK6") (pin "1") (pinfunction "A_1") (pintype "passive"))
      (node (ref "R_IN17") (pin "1") (pinfunction "1_1") (pintype "passive"))
    )
    (net (code "73") (name "Net-(OK6A-C)") (class "Default")
      (node (ref "D1") (pin "A") (pinfunction "A_A") (pintype "passive"))
      (node (ref "OK6") (pin "2") (pinfunction "C_2") (pintype "passive"))
      (node (ref "U$2") (pin "P$2") (pinfunction "P$2_P$2") (pintype "bidirectional"))
    )
    (net (code "74") (name "Net-(OK6B-A)") (class "Default")
      (node (ref "D3") (pin "C") (pinfunction "C_C") (pintype "passive"))
      (node (ref "OK6") (pin "3") (pinfunction "A_3") (pintype "passive"))
      (node (ref "R_IN18") (pin "1") (pinfunction "1_1") (pintype "passive"))
    )
    (net (code "75") (name "Net-(OK6B-C)") (class "Default")
      (node (ref "D3") (pin "A") (pinfunction "A_A") (pintype "passive"))
      (node (ref "OK6") (pin "4") (pinfunction "C_4") (pintype "passive"))
      (node (ref "U$3") (pin "P$2") (pinfunction "P$2_P$2") (pintype "bidirectional"))
    )
    (net (code "76") (name "Net-(Q1-B)") (class "Default")
      (node (ref "Q1") (pin "1") (pinfunction "B_1") (pintype "passive"))
      (node (ref "Q2") (pin "1") (pinfunction "B_1") (pintype "passive"))
      (node (ref "R5") (pin "1") (pinfunction "1_1") (pintype "passive"))
    )
    (net (code "77") (name "Net-(Q1-E)") (class "Default")
      (node (ref "Q1") (pin "2") (pinfunction "E_2") (pintype "passive"))
      (node (ref "Q2") (pin "2") (pinfunction "E_2") (pintype "passive"))
      (node (ref "R6") (pin "2") (pinfunction "2_2") (pintype "passive"))
    )
    (net (code "78") (name "Net-(Q3-B)") (class "Default")
      (node (ref "Q3") (pin "1") (pinfunction "B_1") (pintype "passive"))
      (node (ref "Q4") (pin "1") (pinfunction "B_1") (pintype "passive"))
      (node (ref "R7") (pin "1") (pinfunction "1_1") (pintype "passive"))
    )
    (net (code "79") (name "Net-(Q3-E)") (class "Default")
      (node (ref "Q3") (pin "2") (pinfunction "E_2") (pintype "passive"))
      (node (ref "Q4") (pin "2") (pinfunction "E_2") (pintype "passive"))
      (node (ref "R8") (pin "2") (pinfunction "2_2") (pintype "passive"))
    )
    (net (code "80") (name "Net-(Q5-B)") (class "Default")
      (node (ref "Q5") (pin "1") (pinfunction "B_1") (pintype "passive"))
      (node (ref "Q6") (pin "1") (pinfunction "B_1") (pintype "passive"))
      (node (ref "R9") (pin "1") (pinfunction "1_1") (pintype "passive"))
    )
    (net (code "81") (name "Net-(Q5-E)") (class "Default")
      (node (ref "Q5") (pin "2") (pinfunction "E_2") (pintype "passive"))
      (node (ref "Q6") (pin "2") (pinfunction "E_2") (pintype "passive"))
      (node (ref "R10") (pin "2") (pinfunction "2_2") (pintype "passive"))
    )
    (net (code "82") (name "Net-(R_IN17-Pad2)") (class "Default")
      (node (ref "R_IN17") (pin "2") (pinfunction "2_2") (pintype "passive"))
      (node (ref "U$2") (pin "P$1") (pinfunction "P$1_P$1") (pintype "bidirectional"))
    )
    (net (code "83") (name "Net-(R_IN18-Pad2)") (class "Default")
      (node (ref "R_IN18") (pin "2") (pinfunction "2_2") (pintype "passive"))
      (node (ref "U$3") (pin "P$1") (pinfunction "P$1_P$1") (pintype "bidirectional"))
    )
    (net (code "84") (name "Net-(U1-PB1(OC1A))") (class "Default")
      (node (ref "R4") (pin "2") (pinfunction "2_2") (pintype "passive"))
      (node (ref "U1") (pin "13") (pinfunction "PB1(OC1A)_13") (pintype "bidirectional"))
    )
    (net (code "85") (name "Net-(U1-PB6(XTAL1{slash}TOSC1))") (class "Default")
      (node (ref "U1") (pin "7") (pinfunction "PB6(XTAL1/TOSC1)_7") (pintype "bidirectional"))
      (node (ref "Y1") (pin "1") (pinfunction "1_1") (pintype "passive"))
    )
    (net (code "86") (name "Net-(U1-PB7(XTAL2{slash}TOSC2))") (class "Default")
      (node (ref "U1") (pin "8") (pinfunction "PB7(XTAL2/TOSC2)_8") (pintype "bidirectional"))
      (node (ref "Y1") (pin "3") (pinfunction "3_3") (pintype "passive"))
    )
    (net (code "87") (name "Net-(U1-PD3(INT1))") (class "Default")
      (node (ref "R1") (pin "2") (pinfunction "2_2") (pintype "passive"))
      (node (ref "U1") (pin "1") (pinfunction "PD3(INT1)_1") (pintype "bidirectional"))
    )
    (net (code "88") (name "Net-(U1-PD5(T1))") (class "Default")
      (node (ref "R2") (pin "2") (pinfunction "2_2") (pintype "passive"))
      (node (ref "U1") (pin "9") (pinfunction "PD5(T1)_9") (pintype "bidirectional"))
    )
    (net (code "89") (name "Net-(U1-PD6(AIN0))") (class "Default")
      (node (ref "R3") (pin "2") (pinfunction "2_2") (pintype "passive"))
      (node (ref "U1") (pin "10") (pinfunction "PD6(AIN0)_10") (pintype "bidirectional"))
    )
    (net (code "90") (name "Net-(X6B-S2)") (class "Default")
      (node (ref "BEAD1") (pin "1") (pinfunction "1_1") (pintype "passive"))
      (node (ref "BEAD2") (pin "1") (pinfunction "1_1") (pintype "passive"))
      (node (ref "X6") (pin "M2") (pinfunction "S2_M2") (pintype "passive"))
      (node (ref "X6") (pin "M3") (pinfunction "S3_M3") (pintype "passive"))
    )
    (net (code "91") (name "unconnected-(IC12-CBUS0-Pad22)") (class "Default")
      (node (ref "IC12") (pin "22") (pinfunction "CBUS0_22") (pintype "bidirectional"))
    )
    (net (code "92") (name "unconnected-(IC12-CBUS1-Pad21)") (class "Default")
      (node (ref "IC12") (pin "21") (pinfunction "CBUS1_21") (pintype "bidirectional"))
    )
    (net (code "93") (name "unconnected-(IC12-CBUS2-Pad10)") (class "Default")
      (node (ref "IC12") (pin "10") (pinfunction "CBUS2_10") (pintype "bidirectional"))
    )
    (net (code "94") (name "unconnected-(IC12-CBUS3-Pad11)") (class "Default")
      (node (ref "IC12") (pin "11") (pinfunction "CBUS3_11") (pintype "bidirectional"))
    )
    (net (code "95") (name "unconnected-(IC12-CBUS4-Pad9)") (class "Default")
      (node (ref "IC12") (pin "9") (pinfunction "CBUS4_9") (pintype "bidirectional"))
    )
    (net (code "96") (name "unconnected-(IC12-OSCI-Pad27)") (class "Default")
      (node (ref "IC12") (pin "27") (pinfunction "OSCI_27") (pintype "input"))
    )
    (net (code "97") (name "unconnected-(IC12-OSCO-Pad28)") (class "Default")
      (node (ref "IC12") (pin "28") (pinfunction "OSCO_28") (pintype "output"))
    )
    (net (code "98") (name "unconnected-(IC12-~{CTS}-Pad8)") (class "Default")
      (node (ref "IC12") (pin "8") (pinfunction "~{CTS}_8") (pintype "input"))
    )
    (net (code "99") (name "unconnected-(IC12-~{DCD}-Pad7)") (class "Default")
      (node (ref "IC12") (pin "7") (pinfunction "~{DCD}_7") (pintype "input"))
    )
    (net (code "100") (name "unconnected-(IC12-~{DSR}-Pad6)") (class "Default")
      (node (ref "IC12") (pin "6") (pinfunction "~{DSR}_6") (pintype "input"))
    )
    (net (code "101") (name "unconnected-(IC12-~{RI}-Pad3)") (class "Default")
      (node (ref "IC12") (pin "3") (pinfunction "~{RI}_3") (pintype "input"))
    )
    (net (code "102") (name "unconnected-(U1-PB2(SS{slash}OC1B)-Pad14)") (class "Default")
      (node (ref "U1") (pin "14") (pinfunction "PB2(SS/OC1B)_14") (pintype "bidirectional"))
    )
    (net (code "103") (name "unconnected-(X6B-S1-PadM1)") (class "Default")
      (node (ref "X6") (pin "M1") (pinfunction "S1_M1") (pintype "passive"))
    )
    (net (code "104") (name "unconnected-(X6B-S4-PadM4)") (class "Default")
      (node (ref "X6") (pin "M4") (pinfunction "S4_M4") (pintype "passive"))
    )
  )
)
